# RHD2216_Adapter.net
KiCad netlist of a schematic drawn in EAGLE
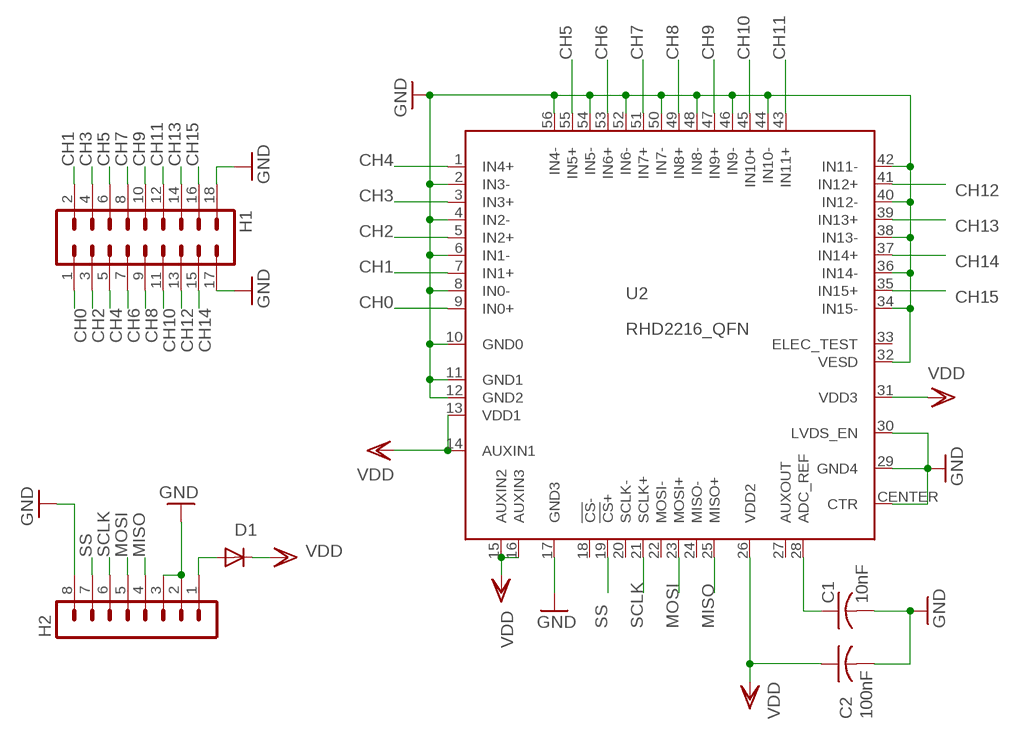
[diagram p0: schematic, sheet 1]

(export (version "E")
  (design (tool "Eeschema 10.0.6"))
  (components
    (comp (ref "C1")
      (value "10nF")
      (footprint "eagle-import:C0402")
      (libsource (lib "eagle-import") (part "C-USC0402"))
    )
    (comp (ref "C2")
      (value "100nF")
      (footprint "eagle-import:C0402")
      (libsource (lib "eagle-import") (part "C-USC0402"))
    )
    (comp (ref "D1")
      (value "DIODE-DO214BA")
      (footprint "eagle-import:DO214BA")
      (libsource (lib "eagle-import") (part "DIODE-DO214BA"))
    )
    (comp (ref "H1")
      (value "MA09-2W")
      (footprint "eagle-import:MA09-2W")
      (libsource (lib "eagle-import") (part "MA09-2W"))
    )
    (comp (ref "H2")
      (value "MA08-1W")
      (footprint "eagle-import:MA08-1W")
      (libsource (lib "eagle-import") (part "MA08-1W"))
    )
    (comp (ref "U2")
      (value "RHD2216_QFN")
      (footprint "eagle-import:QFN56_8_X_8_LARGE")
      (libsource (lib "eagle-import") (part "RHD2216_QFN"))
    )
  )
  (nets
    (net (code "1") (name "/CH0") (class "Default")
      (node (ref "H1") (pin "1") (pinfunction "1_1") (pintype "passive"))
      (node (ref "U2") (pin "9") (pinfunction "IN0+_9") (pintype "input"))
    )
    (net (code "2") (name "/CH1") (class "Default")
      (node (ref "H1") (pin "2") (pinfunction "2_2") (pintype "passive"))
      (node (ref "U2") (pin "7") (pinfunction "IN1+_7") (pintype "input"))
    )
    (net (code "3") (name "/CH2") (class "Default")
      (node (ref "H1") (pin "3") (pinfunction "3_3") (pintype "passive"))
      (node (ref "U2") (pin "5") (pinfunction "IN2+_5") (pintype "input"))
    )
    (net (code "4") (name "/CH3") (class "Default")
      (node (ref "H1") (pin "4") (pinfunction "4_4") (pintype "passive"))
      (node (ref "U2") (pin "3") (pinfunction "IN3+_3") (pintype "input"))
    )
    (net (code "5") (name "/CH4") (class "Default")
      (node (ref "H1") (pin "5") (pinfunction "5_5") (pintype "passive"))
      (node (ref "U2") (pin "1") (pinfunction "IN4+_1") (pintype "input"))
    )
    (net (code "6") (name "/CH5") (class "Default")
      (node (ref "H1") (pin "6") (pinfunction "6_6") (pintype "passive"))
      (node (ref "U2") (pin "55") (pinfunction "IN5+_55") (pintype "input"))
    )
    (net (code "7") (name "/CH6") (class "Default")
      (node (ref "H1") (pin "7") (pinfunction "7_7") (pintype "passive"))
      (node (ref "U2") (pin "53") (pinfunction "IN6+_53") (pintype "input"))
    )
    (net (code "8") (name "/CH7") (class "Default")
      (node (ref "H1") (pin "8") (pinfunction "8_8") (pintype "passive"))
      (node (ref "U2") (pin "51") (pinfunction "IN7+_51") (pintype "input"))
    )
    (net (code "9") (name "/CH8") (class "Default")
      (node (ref "H1") (pin "9") (pinfunction "9_9") (pintype "passive"))
      (node (ref "U2") (pin "49") (pinfunction "IN8+_49") (pintype "input"))
    )
    (net (code "10") (name "/CH9") (class "Default")
      (node (ref "H1") (pin "10") (pinfunction "10_10") (pintype "passive"))
      (node (ref "U2") (pin "47") (pinfunction "IN9+_47") (pintype "input"))
    )
    (net (code "11") (name "/CH10") (class "Default")
      (node (ref "H1") (pin "11") (pinfunction "11_11") (pintype "passive"))
      (node (ref "U2") (pin "45") (pinfunction "IN10+_45") (pintype "input"))
    )
    (net (code "12") (name "/CH11") (class "Default")
      (node (ref "H1") (pin "12") (pinfunction "12_12") (pintype "passive"))
      (node (ref "U2") (pin "43") (pinfunction "IN11+_43") (pintype "input"))
    )
    (net (code "13") (name "/CH12") (class "Default")
      (node (ref "H1") (pin "13") (pinfunction "13_13") (pintype "passive"))
      (node (ref "U2") (pin "41") (pinfunction "IN12+_41") (pintype "input"))
    )
    (net (code "14") (name "/CH13") (class "Default")
      (node (ref "H1") (pin "14") (pinfunction "14_14") (pintype "passive"))
      (node (ref "U2") (pin "39") (pinfunction "IN13+_39") (pintype "input"))
    )
    (net (code "15") (name "/CH14") (class "Default")
      (node (ref "H1") (pin "15") (pinfunction "15_15") (pintype "passive"))
      (node (ref "U2") (pin "37") (pinfunction "IN14+_37") (pintype "input"))
    )
    (net (code "16") (name "/CH15") (class "Default")
      (node (ref "H1") (pin "16") (pinfunction "16_16") (pintype "passive"))
      (node (ref "U2") (pin "35") (pinfunction "IN15+_35") (pintype "input"))
    )
    (net (code "17") (name "/MISO") (class "Default")
      (node (ref "H2") (pin "4") (pinfunction "4_4") (pintype "passive"))
      (node (ref "U2") (pin "25") (pinfunction "MISO+_25") (pintype "output"))
    )
    (net (code "18") (name "/MOSI") (class "Default")
      (node (ref "H2") (pin "5") (pinfunction "5_5") (pintype "passive"))
      (node (ref "U2") (pin "23") (pinfunction "MOSI+_23") (pintype "input"))
    )
    (net (code "19") (name "/SCLK") (class "Default")
      (node (ref "H2") (pin "6") (pinfunction "6_6") (pintype "passive"))
      (node (ref "U2") (pin "21") (pinfunction "SCLK+_21") (pintype "input"))
    )
    (net (code "20") (name "/SS") (class "Default")
      (node (ref "H2") (pin "7") (pinfunction "7_7") (pintype "passive"))
      (node (ref "U2") (pin "19") (pinfunction "~{CS}+_19") (pintype "input"))
    )
    (net (code "21") (name "GND") (class "Default")
      (node (ref "C1") (pin "2") (pinfunction "2_2") (pintype "passive"))
      (node (ref "C2") (pin "2") (pinfunction "2_2") (pintype "passive"))
      (node (ref "H1") (pin "17") (pinfunction "17_17") (pintype "passive"))
      (node (ref "H1") (pin "18") (pinfunction "18_18") (pintype "passive"))
      (node (ref "H2") (pin "2") (pinfunction "2_2") (pintype "passive"))
      (node (ref "H2") (pin "3") (pinfunction "3_3") (pintype "passive"))
      (node (ref "H2") (pin "8") (pinfunction "8_8") (pintype "passive"))
      (node (ref "U2") (pin "10") (pinfunction "GND0_10") (pintype "input"))
      (node (ref "U2") (pin "11") (pinfunction "GND1_11") (pintype "power_in"))
      (node (ref "U2") (pin "12") (pinfunction "GND2_12") (pintype "power_in"))
      (node (ref "U2") (pin "17") (pinfunction "GND3_17") (pintype "power_in"))
      (node (ref "U2") (pin "2") (pinfunction "IN3-_2") (pintype "input"))
      (node (ref "U2") (pin "29") (pinfunction "GND4_29") (pintype "power_in"))
      (node (ref "U2") (pin "30") (pinfunction "LVDS_EN_30") (pintype "input"))
      (node (ref "U2") (pin "32") (pinfunction "VESD_32") (pintype "power_in"))
      (node (ref "U2") (pin "34") (pinfunction "IN15-_34") (pintype "input"))
      (node (ref "U2") (pin "36") (pinfunction "IN14-_36") (pintype "input"))
      (node (ref "U2") (pin "38") (pinfunction "IN13-_38") (pintype "input"))
      (node (ref "U2") (pin "4") (pinfunction "IN2-_4") (pintype "input"))
      (node (ref "U2") (pin "40") (pinfunction "IN12-_40") (pintype "input"))
      (node (ref "U2") (pin "42") (pinfunction "IN11-_42") (pintype "input"))
      (node (ref "U2") (pin "44") (pinfunction "IN10-_44") (pintype "input"))
      (node (ref "U2") (pin "46") (pinfunction "IN9-_46") (pintype "input"))
      (node (ref "U2") (pin "48") (pinfunction "IN8-_48") (pintype "input"))
      (node (ref "U2") (pin "50") (pinfunction "IN7-_50") (pintype "input"))
      (node (ref "U2") (pin "52") (pinfunction "IN6-_52") (pintype "input"))
      (node (ref "U2") (pin "54") (pinfunction "IN5-_54") (pintype "input"))
      (node (ref "U2") (pin "56") (pinfunction "IN4-_56") (pintype "input"))
      (node (ref "U2") (pin "6") (pinfunction "IN1-_6") (pintype "input"))
      (node (ref "U2") (pin "8") (pinfunction "IN0-_8") (pintype "input"))
      (node (ref "U2") (pin "CENTER") (pinfunction "CTR_CENTER") (pintype "power_in"))
    )
    (net (code "22") (name "Net-(D1-PadA)") (class "Default")
      (node (ref "D1") (pin "A") (pinfunction "A_A") (pintype "passive"))
      (node (ref "H2") (pin "1") (pinfunction "1_1") (pintype "passive"))
    )
    (net (code "23") (name "Net-(U2-ADC_REF)") (class "Default")
      (node (ref "C1") (pin "1") (pinfunction "1_1") (pintype "passive"))
      (node (ref "U2") (pin "28") (pinfunction "ADC_REF_28") (pintype "passive"))
    )
    (net (code "24") (name "VDD") (class "Default")
      (node (ref "C2") (pin "1") (pinfunction "1_1") (pintype "passive"))
      (node (ref "D1") (pin "C") (pinfunction "C_C") (pintype "passive"))
      (node (ref "U2") (pin "13") (pinfunction "VDD1_13") (pintype "power_in"))
      (node (ref "U2") (pin "14") (pinfunction "AUXIN1_14") (pintype "input"))
      (node (ref "U2") (pin "15") (pinfunction "AUXIN2_15") (pintype "input"))
      (node (ref "U2") (pin "16") (pinfunction "AUXIN3_16") (pintype "input"))
      (node (ref "U2") (pin "26") (pinfunction "VDD2_26") (pintype "power_in"))
      (node (ref "U2") (pin "31") (pinfunction "VDD3_31") (pintype "power_in"))
    )
    (net (code "25") (name "unconnected-(U2-AUXOUT-Pad27)") (class "Default")
      (node (ref "U2") (pin "27") (pinfunction "AUXOUT_27") (pintype "tri_state"))
    )
    (net (code "26") (name "unconnected-(U2-ELEC_TEST-Pad33)") (class "Default")
      (node (ref "U2") (pin "33") (pinfunction "ELEC_TEST_33") (pintype "input"))
    )
    (net (code "27") (name "unconnected-(U2-MISO--Pad24)") (class "Default")
      (node (ref "U2") (pin "24") (pinfunction "MISO-_24") (pintype "output"))
    )
    (net (code "28") (name "unconnected-(U2-MOSI--Pad22)") (class "Default")
      (node (ref "U2") (pin "22") (pinfunction "MOSI-_22") (pintype "input"))
    )
    (net (code "29") (name "unconnected-(U2-SCLK--Pad20)") (class "Default")
      (node (ref "U2") (pin "20") (pinfunction "SCLK-_20") (pintype "input"))
    )
    (net (code "30") (name "unconnected-(U2-~{CS}--Pad18)") (class "Default")
      (node (ref "U2") (pin "18") (pinfunction "~{CS}-_18") (pintype "input"))
    )
  )
)
